# Stanford_Metro_Mini.net
KiCad netlist of a schematic drawn in EAGLE
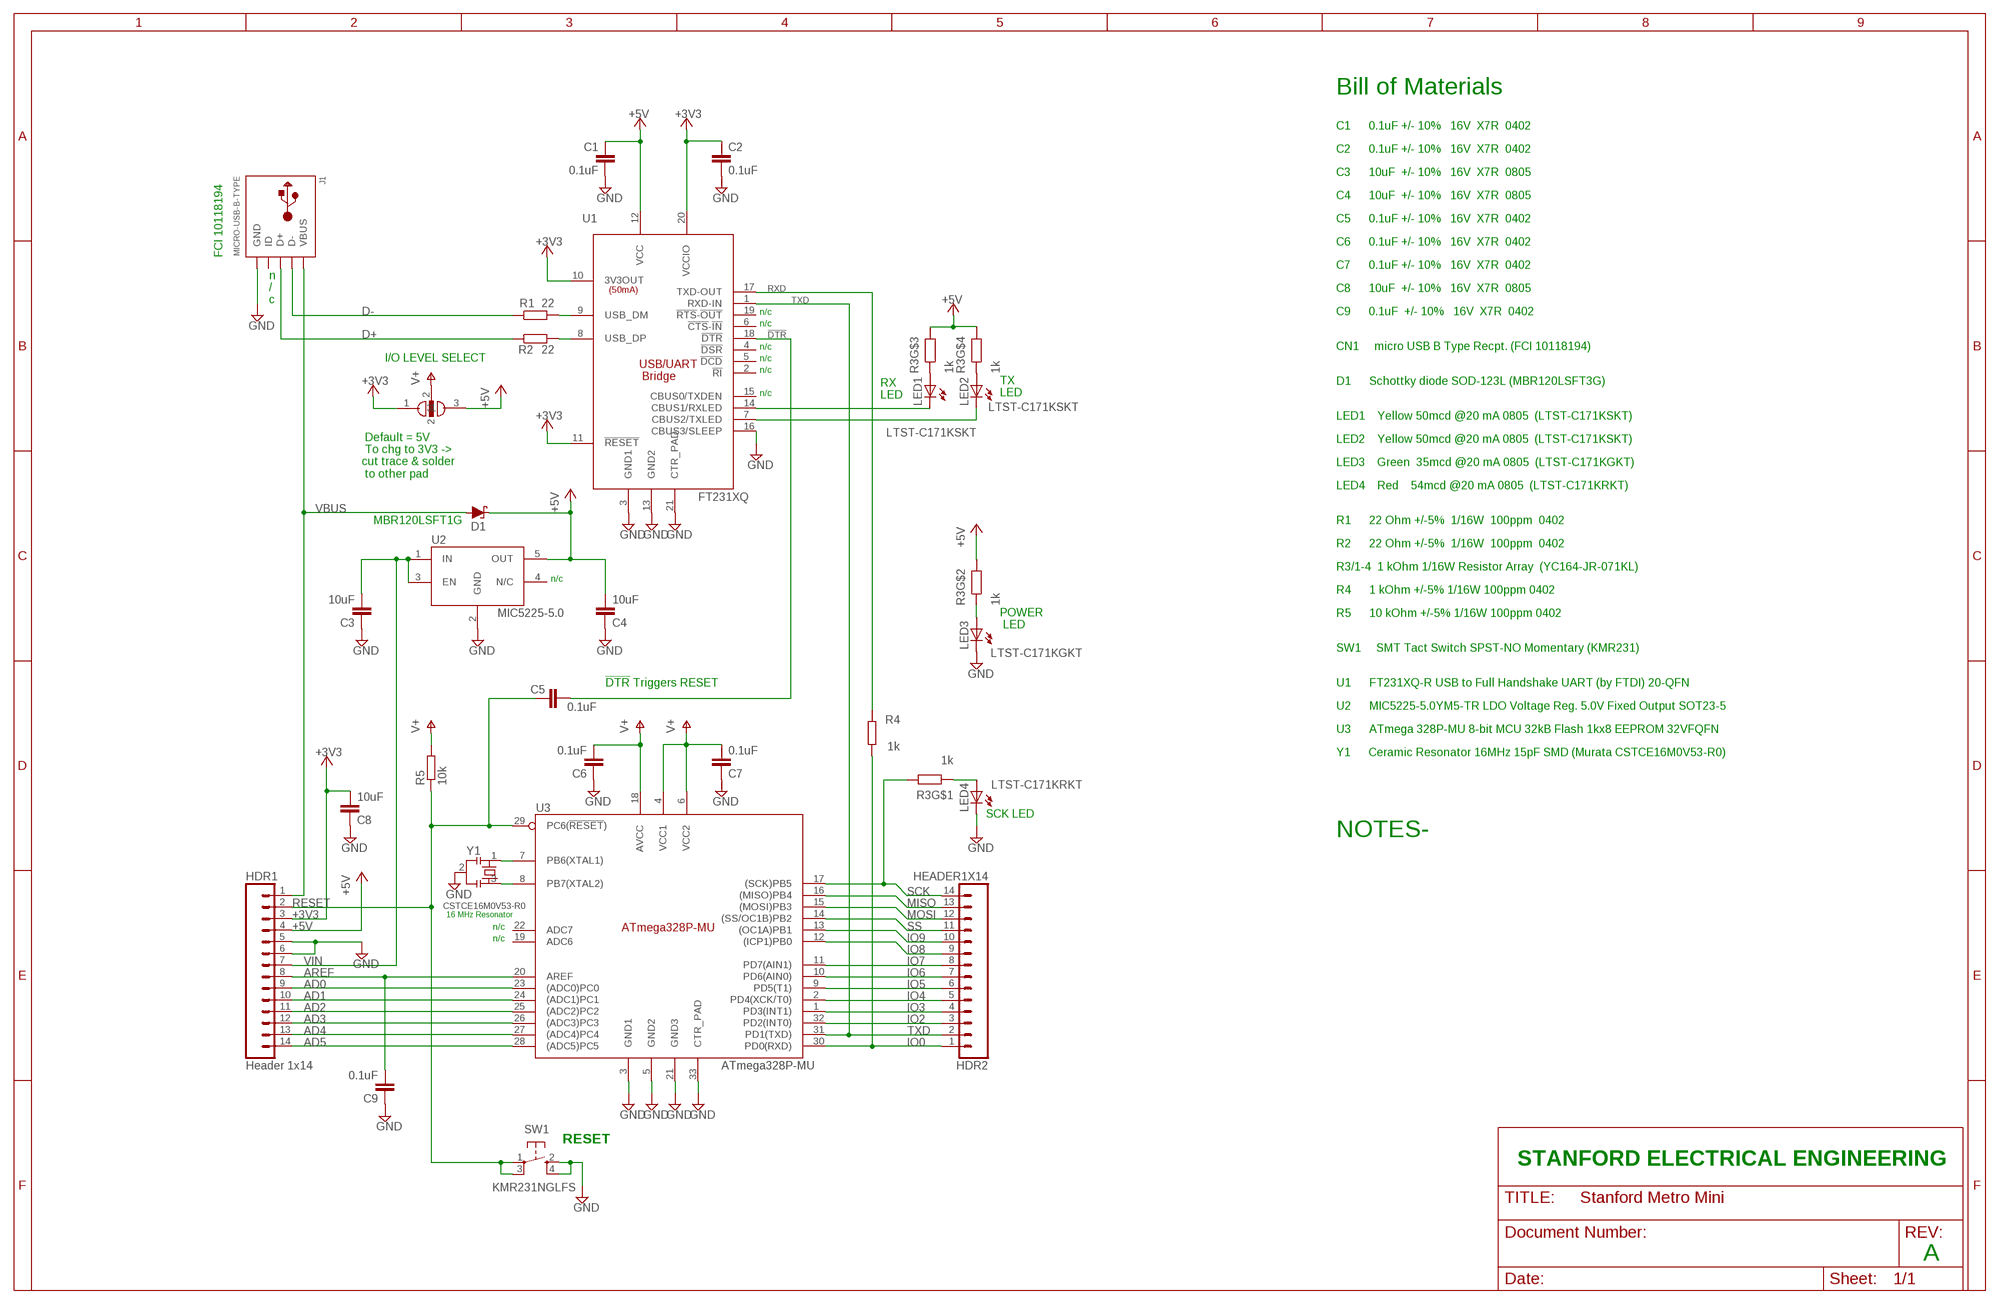
[diagram p0: schematic, sheet 1]

(export (version "E")
  (design (tool "Eeschema 10.0.6"))
  (components
    (comp (ref "C1")
      (value "0.1uF")
      (footprint "eagle-import:C0402")
      (libsource (lib "eagle-import") (part "C-EUC0402"))
    )
    (comp (ref "C2")
      (value "0.1uF")
      (footprint "eagle-import:C0402")
      (libsource (lib "eagle-import") (part "C-EUC0402"))
    )
    (comp (ref "C3")
      (value "10uF")
      (footprint "eagle-import:C0805")
      (libsource (lib "eagle-import") (part "C-EUC0805"))
    )
    (comp (ref "C4")
      (value "10uF")
      (footprint "eagle-import:C0805")
      (libsource (lib "eagle-import") (part "C-EUC0805"))
    )
    (comp (ref "C5")
      (value "0.1uF")
      (footprint "eagle-import:C0402")
      (libsource (lib "eagle-import") (part "C-EUC0402"))
    )
    (comp (ref "C6")
      (value "0.1uF")
      (footprint "eagle-import:C0402")
      (libsource (lib "eagle-import") (part "C-EUC0402"))
    )
    (comp (ref "C7")
      (value "0.1uF")
      (footprint "eagle-import:C0402")
      (libsource (lib "eagle-import") (part "C-EUC0402"))
    )
    (comp (ref "C8")
      (value "10uF")
      (footprint "eagle-import:C0805")
      (libsource (lib "eagle-import") (part "C-EUC0805"))
    )
    (comp (ref "C9")
      (value "0.1uF")
      (footprint "eagle-import:C0402")
      (libsource (lib "eagle-import") (part "C-EUC0402"))
    )
    (comp (ref "D1")
      (value "SCHOTTKY")
      (footprint "eagle-import:SOD123")
      (libsource (lib "eagle-import") (part "SCHOTTKY"))
    )
    (comp (ref "HDR1")
      (value "Header 1x14")
      (footprint "eagle-import:1X14")
      (libsource (lib "eagle-import") (part "HEADER1X14"))
    )
    (comp (ref "HDR2")
      (value "HEADER1X14")
      (footprint "eagle-import:1X14")
      (libsource (lib "eagle-import") (part "HEADER1X14"))
    )
    (comp (ref "J1")
      (value "MICRO-USB-B-TYPE")
      (footprint "eagle-import:10118194-MICRO-USB")
      (libsource (lib "eagle-import") (part "MICRO-USB-B-TYPE"))
    )
    (comp (ref "LED1")
      (value "LTST-C171KSKT")
      (footprint "eagle-import:CHIPLED_0805")
      (libsource (lib "eagle-import") (part "LEDCHIPLED_0805"))
    )
    (comp (ref "LED2")
      (value "LTST-C171KSKT")
      (footprint "eagle-import:CHIPLED_0805")
      (libsource (lib "eagle-import") (part "LEDCHIPLED_0805"))
    )
    (comp (ref "LED3")
      (value "LTST-C171KGKT")
      (footprint "eagle-import:CHIPLED_0805")
      (libsource (lib "eagle-import") (part "LEDCHIPLED_0805"))
    )
    (comp (ref "LED4")
      (value "LTST-C171KRKT")
      (footprint "eagle-import:CHIPLED_0805")
      (libsource (lib "eagle-import") (part "LEDCHIPLED_0805"))
    )
    (comp (ref "R1")
      (value "22")
      (footprint "eagle-import:R0402")
      (libsource (lib "eagle-import") (part "R-EU_R0402"))
    )
    (comp (ref "R2")
      (value "22")
      (footprint "eagle-import:R0402")
      (libsource (lib "eagle-import") (part "R-EU_R0402"))
    )
    (comp (ref "R3")
      (value "1k")
      (footprint "eagle-import:R-ARRAY")
      (libsource (lib "eagle-import") (part "R-ARRAY"))
    )
    (comp (ref "R4")
      (value "1k")
      (footprint "eagle-import:R0402")
      (libsource (lib "eagle-import") (part "R-EU_R0402"))
    )
    (comp (ref "R5")
      (value "10k")
      (footprint "eagle-import:R0402")
      (libsource (lib "eagle-import") (part "R-EU_R0402"))
    )
    (comp (ref "SW1")
      (value "KMR231NGLFS")
      (footprint "eagle-import:KMR2")
      (libsource (lib "eagle-import") (part "SPST_TACT-KMR2"))
    )
    (comp (ref "U$1")
      (value "V_SELECT")
      (footprint "eagle-import:V_SELECT")
      (libsource (lib "eagle-import") (part "V_SELECT"))
    )
    (comp (ref "U1")
      (value "FT231XQ")
      (footprint "eagle-import:QFN20")
      (libsource (lib "eagle-import") (part "FT231XQ"))
    )
    (comp (ref "U2")
      (value "MIC5225-5.0")
      (footprint "eagle-import:SOT23-5")
      (libsource (lib "eagle-import") (part "MIC5225-5.0"))
    )
    (comp (ref "U3")
      (value "ATmega328P-MU")
      (footprint "eagle-import:VQFN-32_CTR-PAD")
      (libsource (lib "eagle-import") (part "ATMEGA328P-MU"))
    )
    (comp (ref "Y1")
      (value "CSTCE16M0V53-R0")
      (footprint "eagle-import:CSTCE")
      (libsource (lib "eagle-import") (part "CSTCE"))
    )
  )
  (nets
    (net (code "1") (name "+3V3") (class "Default")
      (node (ref "C2") (pin "1") (pinfunction "1_1") (pintype "passive"))
      (node (ref "C8") (pin "2") (pinfunction "2_2") (pintype "passive"))
      (node (ref "HDR1") (pin "3") (pinfunction "3_3") (pintype "passive"))
      (node (ref "U$1") (pin "1") (pinfunction "1_1") (pintype "bidirectional"))
      (node (ref "U1") (pin "10") (pinfunction "3V3OUT_10") (pintype "power_in"))
      (node (ref "U1") (pin "11") (pinfunction "~{RESET}_11") (pintype "bidirectional"))
      (node (ref "U1") (pin "20") (pinfunction "VCCIO_20") (pintype "power_in"))
    )
    (net (code "2") (name "+5V") (class "Default")
      (node (ref "C1") (pin "1") (pinfunction "1_1") (pintype "passive"))
      (node (ref "C4") (pin "2") (pinfunction "2_2") (pintype "passive"))
      (node (ref "D1") (pin "1") (pinfunction "C_1") (pintype "passive"))
      (node (ref "HDR1") (pin "4") (pinfunction "4_4") (pintype "passive"))
      (node (ref "R3") (pin "2B") (pinfunction "B_2B") (pintype "bidirectional"))
      (node (ref "R3") (pin "3B") (pinfunction "B_3B") (pintype "bidirectional"))
      (node (ref "R3") (pin "4B") (pinfunction "B_4B") (pintype "bidirectional"))
      (node (ref "U$1") (pin "3") (pinfunction "3_3") (pintype "bidirectional"))
      (node (ref "U1") (pin "12") (pinfunction "VCC_12") (pintype "power_in"))
      (node (ref "U2") (pin "5") (pinfunction "OUT_5") (pintype "bidirectional"))
    )
    (net (code "3") (name "/AD0") (class "Default")
      (node (ref "HDR1") (pin "9") (pinfunction "9_9") (pintype "passive"))
      (node (ref "U3") (pin "23") (pinfunction "(ADC0)PC0_23") (pintype "bidirectional"))
    )
    (net (code "4") (name "/AD1") (class "Default")
      (node (ref "HDR1") (pin "10") (pinfunction "10_10") (pintype "passive"))
      (node (ref "U3") (pin "24") (pinfunction "(ADC1)PC1_24") (pintype "bidirectional"))
    )
    (net (code "5") (name "/AD2") (class "Default")
      (node (ref "HDR1") (pin "11") (pinfunction "11_11") (pintype "passive"))
      (node (ref "U3") (pin "25") (pinfunction "(ADC2)PC2_25") (pintype "bidirectional"))
    )
    (net (code "6") (name "/AD3") (class "Default")
      (node (ref "HDR1") (pin "12") (pinfunction "12_12") (pintype "passive"))
      (node (ref "U3") (pin "26") (pinfunction "(ADC3)PC3_26") (pintype "bidirectional"))
    )
    (net (code "7") (name "/AD4") (class "Default")
      (node (ref "HDR1") (pin "13") (pinfunction "13_13") (pintype "passive"))
      (node (ref "U3") (pin "27") (pinfunction "(ADC4)PC4_27") (pintype "bidirectional"))
    )
    (net (code "8") (name "/AD5") (class "Default")
      (node (ref "HDR1") (pin "14") (pinfunction "14_14") (pintype "passive"))
      (node (ref "U3") (pin "28") (pinfunction "(ADC5)PC5_28") (pintype "bidirectional"))
    )
    (net (code "9") (name "/AREF") (class "Default")
      (node (ref "C9") (pin "2") (pinfunction "2_2") (pintype "passive"))
      (node (ref "HDR1") (pin "8") (pinfunction "8_8") (pintype "passive"))
      (node (ref "U3") (pin "20") (pinfunction "AREF_20") (pintype "bidirectional"))
    )
    (net (code "10") (name "/D+") (class "Default")
      (node (ref "J1") (pin "3") (pinfunction "D+_3") (pintype "bidirectional"))
      (node (ref "R2") (pin "1") (pinfunction "1_1") (pintype "passive"))
    )
    (net (code "11") (name "/D-") (class "Default")
      (node (ref "J1") (pin "2") (pinfunction "D-_2") (pintype "bidirectional"))
      (node (ref "R1") (pin "1") (pinfunction "1_1") (pintype "passive"))
    )
    (net (code "12") (name "/IO0") (class "Default")
      (node (ref "HDR2") (pin "1") (pinfunction "1_1") (pintype "passive"))
      (node (ref "R4") (pin "1") (pinfunction "1_1") (pintype "passive"))
      (node (ref "U3") (pin "30") (pinfunction "PD0(RXD)_30") (pintype "bidirectional"))
    )
    (net (code "13") (name "/IO2") (class "Default")
      (node (ref "HDR2") (pin "3") (pinfunction "3_3") (pintype "passive"))
      (node (ref "U3") (pin "32") (pinfunction "PD2(INT0)_32") (pintype "bidirectional"))
    )
    (net (code "14") (name "/IO3") (class "Default")
      (node (ref "HDR2") (pin "4") (pinfunction "4_4") (pintype "passive"))
      (node (ref "U3") (pin "1") (pinfunction "PD3(INT1)_1") (pintype "bidirectional"))
    )
    (net (code "15") (name "/IO4") (class "Default")
      (node (ref "HDR2") (pin "5") (pinfunction "5_5") (pintype "passive"))
      (node (ref "U3") (pin "2") (pinfunction "PD4(XCK/T0)_2") (pintype "bidirectional"))
    )
    (net (code "16") (name "/IO5") (class "Default")
      (node (ref "HDR2") (pin "6") (pinfunction "6_6") (pintype "passive"))
      (node (ref "U3") (pin "9") (pinfunction "PD5(T1)_9") (pintype "bidirectional"))
    )
    (net (code "17") (name "/IO6") (class "Default")
      (node (ref "HDR2") (pin "7") (pinfunction "7_7") (pintype "passive"))
      (node (ref "U3") (pin "10") (pinfunction "PD6(AIN0)_10") (pintype "bidirectional"))
    )
    (net (code "18") (name "/IO7") (class "Default")
      (node (ref "HDR2") (pin "8") (pinfunction "8_8") (pintype "passive"))
      (node (ref "U3") (pin "11") (pinfunction "PD7(AIN1)_11") (pintype "bidirectional"))
    )
    (net (code "19") (name "/IO8") (class "Default")
      (node (ref "HDR2") (pin "9") (pinfunction "9_9") (pintype "passive"))
      (node (ref "U3") (pin "12") (pinfunction "(ICP1)PB0_12") (pintype "bidirectional"))
    )
    (net (code "20") (name "/IO9") (class "Default")
      (node (ref "HDR2") (pin "10") (pinfunction "10_10") (pintype "passive"))
      (node (ref "U3") (pin "13") (pinfunction "(OC1A)PB1_13") (pintype "bidirectional"))
    )
    (net (code "21") (name "/MISO") (class "Default")
      (node (ref "HDR2") (pin "13") (pinfunction "13_13") (pintype "passive"))
      (node (ref "U3") (pin "16") (pinfunction "(MISO)PB4_16") (pintype "bidirectional"))
    )
    (net (code "22") (name "/MOSI") (class "Default")
      (node (ref "HDR2") (pin "12") (pinfunction "12_12") (pintype "passive"))
      (node (ref "U3") (pin "15") (pinfunction "(MOSI)PB3_15") (pintype "bidirectional"))
    )
    (net (code "23") (name "/RESET") (class "Default")
      (node (ref "C5") (pin "1") (pinfunction "1_1") (pintype "passive"))
      (node (ref "HDR1") (pin "2") (pinfunction "2_2") (pintype "passive"))
      (node (ref "R5") (pin "1") (pinfunction "1_1") (pintype "passive"))
      (node (ref "SW1") (pin "1") (pinfunction "P_1") (pintype "passive"))
      (node (ref "SW1") (pin "3") (pinfunction "P1_3") (pintype "passive"))
      (node (ref "U3") (pin "29") (pinfunction "PC6(~{RESET})_29") (pintype "bidirectional"))
    )
    (net (code "24") (name "/RXD") (class "Default")
      (node (ref "R4") (pin "2") (pinfunction "2_2") (pintype "passive"))
      (node (ref "U1") (pin "17") (pinfunction "TXD-OUT_17") (pintype "bidirectional"))
    )
    (net (code "25") (name "/SCK") (class "Default")
      (node (ref "HDR2") (pin "14") (pinfunction "14_14") (pintype "passive"))
      (node (ref "R3") (pin "1B") (pinfunction "B_1B") (pintype "bidirectional"))
      (node (ref "U3") (pin "17") (pinfunction "(SCK)PB5_17") (pintype "bidirectional"))
    )
    (net (code "26") (name "/SS") (class "Default")
      (node (ref "HDR2") (pin "11") (pinfunction "11_11") (pintype "passive"))
      (node (ref "U3") (pin "14") (pinfunction "(SS/OC1B)PB2_14") (pintype "bidirectional"))
    )
    (net (code "27") (name "/TXD") (class "Default")
      (node (ref "HDR2") (pin "2") (pinfunction "2_2") (pintype "passive"))
      (node (ref "U1") (pin "1") (pinfunction "RXD-IN_1") (pintype "bidirectional"))
      (node (ref "U3") (pin "31") (pinfunction "PD1(TXD)_31") (pintype "bidirectional"))
    )
    (net (code "28") (name "/VBUS") (class "Default")
      (node (ref "D1") (pin "2") (pinfunction "A_2") (pintype "passive"))
      (node (ref "HDR1") (pin "1") (pinfunction "1_1") (pintype "passive"))
      (node (ref "J1") (pin "1") (pinfunction "VBUS_1") (pintype "power_in"))
    )
    (net (code "29") (name "/VIN") (class "Default")
      (node (ref "C3") (pin "2") (pinfunction "2_2") (pintype "passive"))
      (node (ref "HDR1") (pin "7") (pinfunction "7_7") (pintype "passive"))
      (node (ref "U2") (pin "1") (pinfunction "IN_1") (pintype "bidirectional"))
      (node (ref "U2") (pin "3") (pinfunction "EN_3") (pintype "bidirectional"))
    )
    (net (code "30") (name "/~{DTR}") (class "Default")
      (node (ref "C5") (pin "2") (pinfunction "2_2") (pintype "passive"))
      (node (ref "U1") (pin "18") (pinfunction "~{DTR}_18") (pintype "bidirectional"))
    )
    (net (code "31") (name "GND") (class "Default")
      (node (ref "C1") (pin "2") (pinfunction "2_2") (pintype "passive"))
      (node (ref "C2") (pin "2") (pinfunction "2_2") (pintype "passive"))
      (node (ref "C3") (pin "1") (pinfunction "1_1") (pintype "passive"))
      (node (ref "C4") (pin "1") (pinfunction "1_1") (pintype "passive"))
      (node (ref "C6") (pin "1") (pinfunction "1_1") (pintype "passive"))
      (node (ref "C7") (pin "1") (pinfunction "1_1") (pintype "passive"))
      (node (ref "C8") (pin "1") (pinfunction "1_1") (pintype "passive"))
      (node (ref "C9") (pin "1") (pinfunction "1_1") (pintype "passive"))
      (node (ref "HDR1") (pin "5") (pinfunction "5_5") (pintype "passive"))
      (node (ref "HDR1") (pin "6") (pinfunction "6_6") (pintype "passive"))
      (node (ref "J1") (pin "5") (pinfunction "GND_5") (pintype "power_in"))
      (node (ref "LED3") (pin "C") (pinfunction "C_C") (pintype "passive"))
      (node (ref "LED4") (pin "C") (pinfunction "C_C") (pintype "passive"))
      (node (ref "SW1") (pin "2") (pinfunction "S_2") (pintype "passive"))
      (node (ref "SW1") (pin "4") (pinfunction "S1_4") (pintype "passive"))
      (node (ref "U1") (pin "13") (pinfunction "GND2_13") (pintype "power_in"))
      (node (ref "U1") (pin "16") (pinfunction "CBUS3/SLEEP_16") (pintype "bidirectional"))
      (node (ref "U1") (pin "21") (pinfunction "CTR_PAD_21") (pintype "power_in"))
      (node (ref "U1") (pin "3") (pinfunction "GND1_3") (pintype "power_in"))
      (node (ref "U2") (pin "2") (pinfunction "GND_2") (pintype "power_in"))
      (node (ref "U3") (pin "21") (pinfunction "GND3_21") (pintype "power_in"))
      (node (ref "U3") (pin "3") (pinfunction "GND1_3") (pintype "power_in"))
      (node (ref "U3") (pin "33") (pinfunction "CTR_PAD_33") (pintype "power_in"))
      (node (ref "U3") (pin "5") (pinfunction "GND2_5") (pintype "power_in"))
      (node (ref "Y1") (pin "2") (pinfunction "2_2") (pintype "passive"))
    )
    (net (code "32") (name "Net-(R3A-A)") (class "Default")
      (node (ref "LED4") (pin "A") (pinfunction "A_A") (pintype "passive"))
      (node (ref "R3") (pin "1A") (pinfunction "A_1A") (pintype "bidirectional"))
    )
    (net (code "33") (name "Net-(R3B-A)") (class "Default")
      (node (ref "LED3") (pin "A") (pinfunction "A_A") (pintype "passive"))
      (node (ref "R3") (pin "2A") (pinfunction "A_2A") (pintype "bidirectional"))
    )
    (net (code "34") (name "Net-(R3C-A)") (class "Default")
      (node (ref "LED1") (pin "A") (pinfunction "A_A") (pintype "passive"))
      (node (ref "R3") (pin "3A") (pinfunction "A_3A") (pintype "bidirectional"))
    )
    (net (code "35") (name "Net-(R3D-A)") (class "Default")
      (node (ref "LED2") (pin "A") (pinfunction "A_A") (pintype "passive"))
      (node (ref "R3") (pin "4A") (pinfunction "A_4A") (pintype "bidirectional"))
    )
    (net (code "36") (name "Net-(U1-CBUS1{slash}RXLED)") (class "Default")
      (node (ref "LED1") (pin "C") (pinfunction "C_C") (pintype "passive"))
      (node (ref "U1") (pin "14") (pinfunction "CBUS1/RXLED_14") (pintype "bidirectional"))
    )
    (net (code "37") (name "Net-(U1-CBUS2{slash}TXLED)") (class "Default")
      (node (ref "LED2") (pin "C") (pinfunction "C_C") (pintype "passive"))
      (node (ref "U1") (pin "7") (pinfunction "CBUS2/TXLED_7") (pintype "bidirectional"))
    )
    (net (code "38") (name "Net-(U1-USB_DM)") (class "Default")
      (node (ref "R1") (pin "2") (pinfunction "2_2") (pintype "passive"))
      (node (ref "U1") (pin "9") (pinfunction "USB_DM_9") (pintype "bidirectional"))
    )
    (net (code "39") (name "Net-(U1-USB_DP)") (class "Default")
      (node (ref "R2") (pin "2") (pinfunction "2_2") (pintype "passive"))
      (node (ref "U1") (pin "8") (pinfunction "USB_DP_8") (pintype "bidirectional"))
    )
    (net (code "40") (name "Net-(U3-PB6(XTAL1))") (class "Default")
      (node (ref "U3") (pin "7") (pinfunction "PB6(XTAL1)_7") (pintype "bidirectional"))
      (node (ref "Y1") (pin "1") (pinfunction "1_1") (pintype "passive"))
    )
    (net (code "41") (name "Net-(U3-PB7(XTAL2))") (class "Default")
      (node (ref "U3") (pin "8") (pinfunction "PB7(XTAL2)_8") (pintype "bidirectional"))
      (node (ref "Y1") (pin "3") (pinfunction "3_3") (pintype "passive"))
    )
    (net (code "42") (name "V+") (class "Default")
      (node (ref "C6") (pin "2") (pinfunction "2_2") (pintype "passive"))
      (node (ref "C7") (pin "2") (pinfunction "2_2") (pintype "passive"))
      (node (ref "R5") (pin "2") (pinfunction "2_2") (pintype "passive"))
      (node (ref "U$1") (pin "2") (pinfunction "2_2") (pintype "bidirectional"))
      (node (ref "U3") (pin "18") (pinfunction "AVCC_18") (pintype "bidirectional"))
      (node (ref "U3") (pin "4") (pinfunction "VCC1_4") (pintype "bidirectional"))
      (node (ref "U3") (pin "6") (pinfunction "VCC2_6") (pintype "bidirectional"))
    )
    (net (code "43") (name "unconnected-(J1-ID-Pad4)") (class "Default")
      (node (ref "J1") (pin "4") (pinfunction "ID_4") (pintype "bidirectional"))
    )
    (net (code "44") (name "unconnected-(U1-CBUS0{slash}TXDEN-Pad15)") (class "Default")
      (node (ref "U1") (pin "15") (pinfunction "CBUS0/TXDEN_15") (pintype "no_connect"))
    )
    (net (code "45") (name "unconnected-(U1-~{CTS}-~{IN}-Pad6)") (class "Default")
      (node (ref "U1") (pin "6") (pinfunction "~{CTS}-~{IN}_6") (pintype "bidirectional"))
    )
    (net (code "46") (name "unconnected-(U1-~{DCD}-Pad5)") (class "Default")
      (node (ref "U1") (pin "5") (pinfunction "~{DCD}_5") (pintype "bidirectional"))
    )
    (net (code "47") (name "unconnected-(U1-~{DSR}-Pad4)") (class "Default")
      (node (ref "U1") (pin "4") (pinfunction "~{DSR}_4") (pintype "bidirectional"))
    )
    (net (code "48") (name "unconnected-(U1-~{RI}-Pad2)") (class "Default")
      (node (ref "U1") (pin "2") (pinfunction "~{RI}_2") (pintype "bidirectional"))
    )
    (net (code "49") (name "unconnected-(U1-~{RTS}-~{OUT}-Pad19)") (class "Default")
      (node (ref "U1") (pin "19") (pinfunction "~{RTS}-~{OUT}_19") (pintype "bidirectional"))
    )
    (net (code "50") (name "unconnected-(U2-N{slash}C-Pad4)") (class "Default")
      (node (ref "U2") (pin "4") (pinfunction "N/C_4") (pintype "passive"))
    )
    (net (code "51") (name "unconnected-(U3-ADC6-Pad19)") (class "Default")
      (node (ref "U3") (pin "19") (pinfunction "ADC6_19") (pintype "bidirectional"))
    )
    (net (code "52") (name "unconnected-(U3-ADC7-Pad22)") (class "Default")
      (node (ref "U3") (pin "22") (pinfunction "ADC7_22") (pintype "bidirectional"))
    )
  )
)
